# stm32f030f4p6.net
KiCad netlist of a schematic drawn in EAGLE
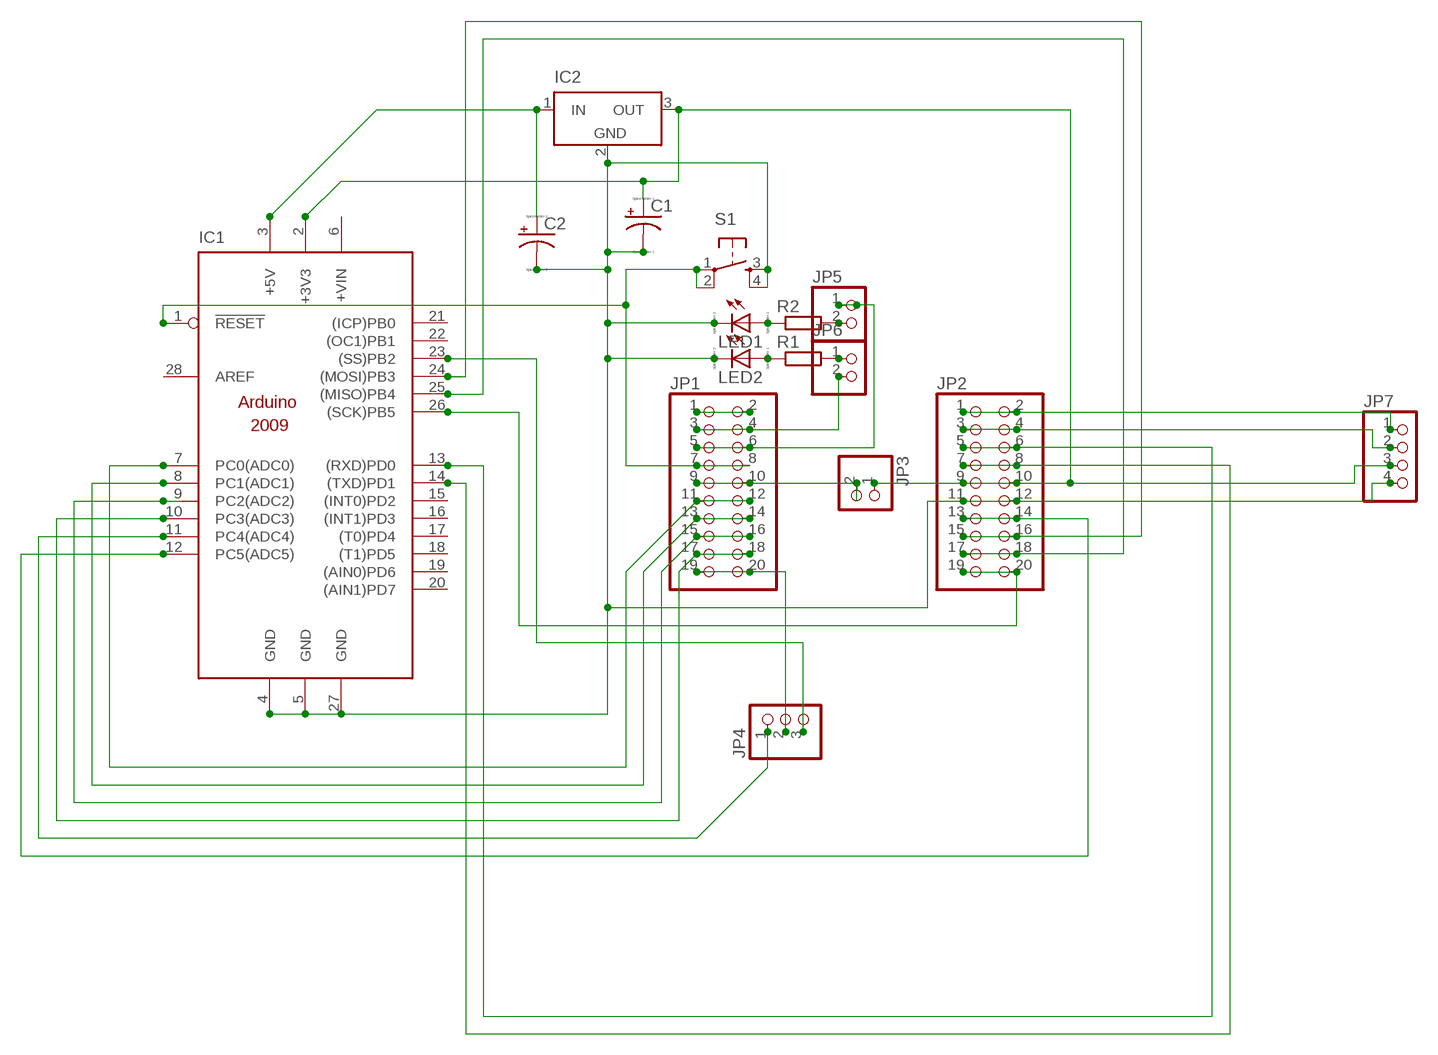
[diagram p0: schematic, sheet 1]

(export (version "E")
  (design (tool "Eeschema 10.0.6"))
  (components
    (comp (ref "C1")
      (value "CPOL-USE3.5-8")
      (footprint "eagle-import:E3,5-8")
      (libsource (lib "eagle-import") (part "CPOL-USE3.5-8"))
    )
    (comp (ref "C2")
      (value "CPOL-USE3.5-8")
      (footprint "eagle-import:E3,5-8")
      (libsource (lib "eagle-import") (part "CPOL-USE3.5-8"))
    )
    (comp (ref "IC1")
      (value "ARDUINO2009_PIN_12")
      (footprint "eagle-import:ARDUINO2009_2")
      (libsource (lib "eagle-import") (part "ARDUINO2009_PIN_12"))
    )
    (comp (ref "IC2")
      (value "LT1129CST5")
      (footprint "eagle-import:SOT223")
      (fields (field (name "MPN") "LT1129CST-5#PBF"))
      (libsource (lib "eagle-import") (part "LT1129CST5"))
    )
    (comp (ref "JP1")
      (value "PINHD-2X10")
      (footprint "eagle-import:2X10")
      (libsource (lib "eagle-import") (part "PINHD-2X10"))
    )
    (comp (ref "JP2")
      (value "PINHD-2X10")
      (footprint "eagle-import:2X10")
      (libsource (lib "eagle-import") (part "PINHD-2X10"))
    )
    (comp (ref "JP3")
      (value "PINHD-1X2")
      (footprint "eagle-import:1X02")
      (libsource (lib "eagle-import") (part "PINHD-1X2"))
    )
    (comp (ref "JP4")
      (value "PINHD-1X3_2.54")
      (footprint "eagle-import:1X03")
      (libsource (lib "eagle-import") (part "PINHD-1X3_2.54"))
    )
    (comp (ref "JP5")
      (value "PINHD-1X2")
      (footprint "eagle-import:1X02")
      (libsource (lib "eagle-import") (part "PINHD-1X2"))
    )
    (comp (ref "JP6")
      (value "PINHD-1X2")
      (footprint "eagle-import:1X02")
      (libsource (lib "eagle-import") (part "PINHD-1X2"))
    )
    (comp (ref "JP7")
      (value "PINHD-1X4")
      (footprint "eagle-import:1X04")
      (libsource (lib "eagle-import") (part "PINHD-1X4"))
    )
    (comp (ref "LED1")
      (value "LED_ELD260")
      (footprint "eagle-import:LED_LD260")
      (libsource (lib "eagle-import") (part "LED_ELD260"))
    )
    (comp (ref "LED2")
      (value "LED_ELD260")
      (footprint "eagle-import:LED_LD260")
      (libsource (lib "eagle-import") (part "LED_ELD260"))
    )
    (comp (ref "R1")
      (value "R-EU_0204/7")
      (footprint "eagle-import:0204_7")
      (libsource (lib "eagle-import") (part "R-EU_0204/7"))
    )
    (comp (ref "R2")
      (value "R-EU_0204/7")
      (footprint "eagle-import:0204_7")
      (libsource (lib "eagle-import") (part "R-EU_0204/7"))
    )
    (comp (ref "S1")
      (value "TAC_SWITCHPTH")
      (footprint "eagle-import:TACTILE-PTH")
      (libsource (lib "eagle-import") (part "TAC_SWITCHPTH"))
    )
  )
  (nets
    (net (code "1") (name "Net-(IC1-(MISO)PB4)") (class "Default")
      (node (ref "IC1") (pin "25") (pinfunction "(MISO)PB4_25") (pintype "bidirectional"))
      (node (ref "JP2") (pin "17") (pinfunction "17_17") (pintype "passive"))
      (node (ref "JP2") (pin "18") (pinfunction "18_18") (pintype "passive"))
    )
    (net (code "2") (name "Net-(IC1-(MOSI)PB3)") (class "Default")
      (node (ref "IC1") (pin "24") (pinfunction "(MOSI)PB3_24") (pintype "bidirectional"))
      (node (ref "JP2") (pin "15") (pinfunction "15_15") (pintype "passive"))
      (node (ref "JP2") (pin "16") (pinfunction "16_16") (pintype "passive"))
    )
    (net (code "3") (name "Net-(IC1-(RXD)PD0)") (class "Default")
      (node (ref "IC1") (pin "13") (pinfunction "(RXD)PD0_13") (pintype "bidirectional"))
      (node (ref "JP2") (pin "5") (pinfunction "5_5") (pintype "passive"))
      (node (ref "JP2") (pin "6") (pinfunction "6_6") (pintype "passive"))
    )
    (net (code "4") (name "Net-(IC1-(SCK)PB5)") (class "Default")
      (node (ref "IC1") (pin "26") (pinfunction "(SCK)PB5_26") (pintype "bidirectional"))
      (node (ref "JP2") (pin "19") (pinfunction "19_19") (pintype "passive"))
      (node (ref "JP2") (pin "20") (pinfunction "20_20") (pintype "passive"))
    )
    (net (code "5") (name "Net-(IC1-(SS)PB2)") (class "Default")
      (node (ref "IC1") (pin "23") (pinfunction "(SS)PB2_23") (pintype "bidirectional"))
      (node (ref "JP4") (pin "3") (pinfunction "3_3") (pintype "passive"))
    )
    (net (code "6") (name "Net-(IC1-(TXD)PD1)") (class "Default")
      (node (ref "IC1") (pin "14") (pinfunction "(TXD)PD1_14") (pintype "bidirectional"))
      (node (ref "JP2") (pin "7") (pinfunction "7_7") (pintype "passive"))
      (node (ref "JP2") (pin "8") (pinfunction "8_8") (pintype "passive"))
    )
    (net (code "7") (name "Net-(IC1-+3V3)") (class "Default")
      (node (ref "C1") (pin "+") (pinfunction "+_+") (pintype "passive"))
      (node (ref "IC1") (pin "2") (pinfunction "+3V3_2") (pintype "power_in"))
      (node (ref "IC2") (pin "3") (pinfunction "OUT_3") (pintype "output"))
      (node (ref "JP2") (pin "10") (pinfunction "10_10") (pintype "passive"))
      (node (ref "JP2") (pin "9") (pinfunction "9_9") (pintype "passive"))
      (node (ref "JP3") (pin "1") (pinfunction "1_1") (pintype "passive"))
      (node (ref "JP7") (pin "3") (pinfunction "3_3") (pintype "passive"))
    )
    (net (code "8") (name "Net-(IC1-+5V)") (class "Default")
      (node (ref "C2") (pin "+") (pinfunction "+_+") (pintype "passive"))
      (node (ref "IC1") (pin "3") (pinfunction "+5V_3") (pintype "power_in"))
      (node (ref "IC2") (pin "1") (pinfunction "IN_1") (pintype "input"))
    )
    (net (code "9") (name "Net-(IC1-PC0(ADC0))") (class "Default")
      (node (ref "IC1") (pin "7") (pinfunction "PC0(ADC0)_7") (pintype "bidirectional"))
      (node (ref "JP1") (pin "11") (pinfunction "11_11") (pintype "passive"))
      (node (ref "JP1") (pin "12") (pinfunction "12_12") (pintype "passive"))
    )
    (net (code "10") (name "Net-(IC1-PC1(ADC1))") (class "Default")
      (node (ref "IC1") (pin "8") (pinfunction "PC1(ADC1)_8") (pintype "bidirectional"))
      (node (ref "JP1") (pin "13") (pinfunction "13_13") (pintype "passive"))
      (node (ref "JP1") (pin "14") (pinfunction "14_14") (pintype "passive"))
    )
    (net (code "11") (name "Net-(IC1-PC2(ADC2))") (class "Default")
      (node (ref "IC1") (pin "9") (pinfunction "PC2(ADC2)_9") (pintype "bidirectional"))
      (node (ref "JP1") (pin "15") (pinfunction "15_15") (pintype "passive"))
      (node (ref "JP1") (pin "16") (pinfunction "16_16") (pintype "passive"))
    )
    (net (code "12") (name "Net-(IC1-PC3(ADC3))") (class "Default")
      (node (ref "IC1") (pin "10") (pinfunction "PC3(ADC3)_10") (pintype "bidirectional"))
      (node (ref "JP1") (pin "17") (pinfunction "17_17") (pintype "passive"))
      (node (ref "JP1") (pin "18") (pinfunction "18_18") (pintype "passive"))
    )
    (net (code "13") (name "Net-(IC1-PC4(ADC4))") (class "Default")
      (node (ref "IC1") (pin "11") (pinfunction "PC4(ADC4)_11") (pintype "bidirectional"))
      (node (ref "JP4") (pin "1") (pinfunction "1_1") (pintype "passive"))
    )
    (net (code "14") (name "Net-(IC1-PC5(ADC5))") (class "Default")
      (node (ref "IC1") (pin "12") (pinfunction "PC5(ADC5)_12") (pintype "bidirectional"))
      (node (ref "JP2") (pin "13") (pinfunction "13_13") (pintype "passive"))
      (node (ref "JP2") (pin "14") (pinfunction "14_14") (pintype "passive"))
    )
    (net (code "15") (name "Net-(IC1-~{RESET})") (class "Default")
      (node (ref "IC1") (pin "1") (pinfunction "~{RESET}_1") (pintype "bidirectional"))
      (node (ref "JP1") (pin "7") (pinfunction "7_7") (pintype "passive"))
      (node (ref "JP1") (pin "8") (pinfunction "8_8") (pintype "passive"))
      (node (ref "S1") (pin "1") (pinfunction "1_1") (pintype "passive"))
      (node (ref "S1") (pin "2") (pinfunction "2_2") (pintype "passive"))
    )
    (net (code "16") (name "Net-(IC2A-GND)") (class "Default")
      (node (ref "C1") (pin "-") (pinfunction "-_-") (pintype "passive"))
      (node (ref "C2") (pin "-") (pinfunction "-_-") (pintype "passive"))
      (node (ref "IC1") (pin "27") (pinfunction "GND_27") (pintype "power_in"))
      (node (ref "IC1") (pin "4") (pinfunction "GND_4") (pintype "power_in"))
      (node (ref "IC1") (pin "5") (pinfunction "GND_5") (pintype "power_in"))
      (node (ref "IC2") (pin "2") (pinfunction "GND_2") (pintype "power_in"))
      (node (ref "JP2") (pin "11") (pinfunction "11_11") (pintype "passive"))
      (node (ref "JP2") (pin "12") (pinfunction "12_12") (pintype "passive"))
      (node (ref "JP7") (pin "4") (pinfunction "4_4") (pintype "passive"))
      (node (ref "LED1") (pin "K") (pinfunction "C_K") (pintype "passive"))
      (node (ref "LED2") (pin "K") (pinfunction "C_K") (pintype "passive"))
      (node (ref "S1") (pin "3") (pinfunction "3_3") (pintype "passive"))
      (node (ref "S1") (pin "4") (pinfunction "4_4") (pintype "passive"))
    )
    (net (code "17") (name "Net-(JP1-Pad1)") (class "Default")
      (node (ref "JP1") (pin "1") (pinfunction "1_1") (pintype "passive"))
      (node (ref "JP1") (pin "2") (pinfunction "2_2") (pintype "passive"))
    )
    (net (code "18") (name "Net-(JP1-Pad3)") (class "Default")
      (node (ref "JP1") (pin "3") (pinfunction "3_3") (pintype "passive"))
      (node (ref "JP1") (pin "4") (pinfunction "4_4") (pintype "passive"))
      (node (ref "JP6") (pin "2") (pinfunction "2_2") (pintype "passive"))
    )
    (net (code "19") (name "Net-(JP1-Pad5)") (class "Default")
      (node (ref "JP1") (pin "5") (pinfunction "5_5") (pintype "passive"))
      (node (ref "JP1") (pin "6") (pinfunction "6_6") (pintype "passive"))
      (node (ref "JP5") (pin "1") (pinfunction "1_1") (pintype "passive"))
    )
    (net (code "20") (name "Net-(JP1-Pad10)") (class "Default")
      (node (ref "JP1") (pin "10") (pinfunction "10_10") (pintype "passive"))
      (node (ref "JP1") (pin "9") (pinfunction "9_9") (pintype "passive"))
      (node (ref "JP3") (pin "2") (pinfunction "2_2") (pintype "passive"))
    )
    (net (code "21") (name "Net-(JP1-Pad19)") (class "Default")
      (node (ref "JP1") (pin "19") (pinfunction "19_19") (pintype "passive"))
      (node (ref "JP1") (pin "20") (pinfunction "20_20") (pintype "passive"))
      (node (ref "JP4") (pin "2") (pinfunction "2_2") (pintype "passive"))
    )
    (net (code "22") (name "Net-(JP2-Pad1)") (class "Default")
      (node (ref "JP2") (pin "1") (pinfunction "1_1") (pintype "passive"))
      (node (ref "JP2") (pin "2") (pinfunction "2_2") (pintype "passive"))
      (node (ref "JP7") (pin "1") (pinfunction "1_1") (pintype "passive"))
    )
    (net (code "23") (name "Net-(JP2-Pad3)") (class "Default")
      (node (ref "JP2") (pin "3") (pinfunction "3_3") (pintype "passive"))
      (node (ref "JP2") (pin "4") (pinfunction "4_4") (pintype "passive"))
      (node (ref "JP7") (pin "2") (pinfunction "2_2") (pintype "passive"))
    )
    (net (code "24") (name "Net-(JP5-Pad2)") (class "Default")
      (node (ref "JP5") (pin "2") (pinfunction "2_2") (pintype "passive"))
      (node (ref "R2") (pin "2") (pinfunction "2_2") (pintype "passive"))
    )
    (net (code "25") (name "Net-(JP6-Pad1)") (class "Default")
      (node (ref "JP6") (pin "1") (pinfunction "1_1") (pintype "passive"))
      (node (ref "R1") (pin "2") (pinfunction "2_2") (pintype "passive"))
    )
    (net (code "26") (name "Net-(LED1-PadA)") (class "Default")
      (node (ref "LED1") (pin "A") (pinfunction "A_A") (pintype "passive"))
      (node (ref "R2") (pin "1") (pinfunction "1_1") (pintype "passive"))
    )
    (net (code "27") (name "Net-(LED2-PadA)") (class "Default")
      (node (ref "LED2") (pin "A") (pinfunction "A_A") (pintype "passive"))
      (node (ref "R1") (pin "1") (pinfunction "1_1") (pintype "passive"))
    )
    (net (code "28") (name "unconnected-(IC1-(AIN0)PD6-Pad19)") (class "Default")
      (node (ref "IC1") (pin "19") (pinfunction "(AIN0)PD6_19") (pintype "bidirectional"))
    )
    (net (code "29") (name "unconnected-(IC1-(AIN1)PD7-Pad20)") (class "Default")
      (node (ref "IC1") (pin "20") (pinfunction "(AIN1)PD7_20") (pintype "bidirectional"))
    )
    (net (code "30") (name "unconnected-(IC1-(ICP)PB0-Pad21)") (class "Default")
      (node (ref "IC1") (pin "21") (pinfunction "(ICP)PB0_21") (pintype "bidirectional"))
    )
    (net (code "31") (name "unconnected-(IC1-(INT0)PD2-Pad15)") (class "Default")
      (node (ref "IC1") (pin "15") (pinfunction "(INT0)PD2_15") (pintype "bidirectional"))
    )
    (net (code "32") (name "unconnected-(IC1-(INT1)PD3-Pad16)") (class "Default")
      (node (ref "IC1") (pin "16") (pinfunction "(INT1)PD3_16") (pintype "bidirectional"))
    )
    (net (code "33") (name "unconnected-(IC1-(OC1)PB1-Pad22)") (class "Default")
      (node (ref "IC1") (pin "22") (pinfunction "(OC1)PB1_22") (pintype "bidirectional"))
    )
    (net (code "34") (name "unconnected-(IC1-(T0)PD4-Pad17)") (class "Default")
      (node (ref "IC1") (pin "17") (pinfunction "(T0)PD4_17") (pintype "bidirectional"))
    )
    (net (code "35") (name "unconnected-(IC1-(T1)PD5-Pad18)") (class "Default")
      (node (ref "IC1") (pin "18") (pinfunction "(T1)PD5_18") (pintype "bidirectional"))
    )
    (net (code "36") (name "unconnected-(IC1-+VIN-Pad6)") (class "Default")
      (node (ref "IC1") (pin "6") (pinfunction "+VIN_6") (pintype "bidirectional"))
    )
    (net (code "37") (name "unconnected-(IC1-AREF-Pad28)") (class "Default")
      (node (ref "IC1") (pin "28") (pinfunction "AREF_28") (pintype "bidirectional"))
    )
  )
)
